# FPGA_1.net
KiCad netlist of a schematic drawn in Altium Designer
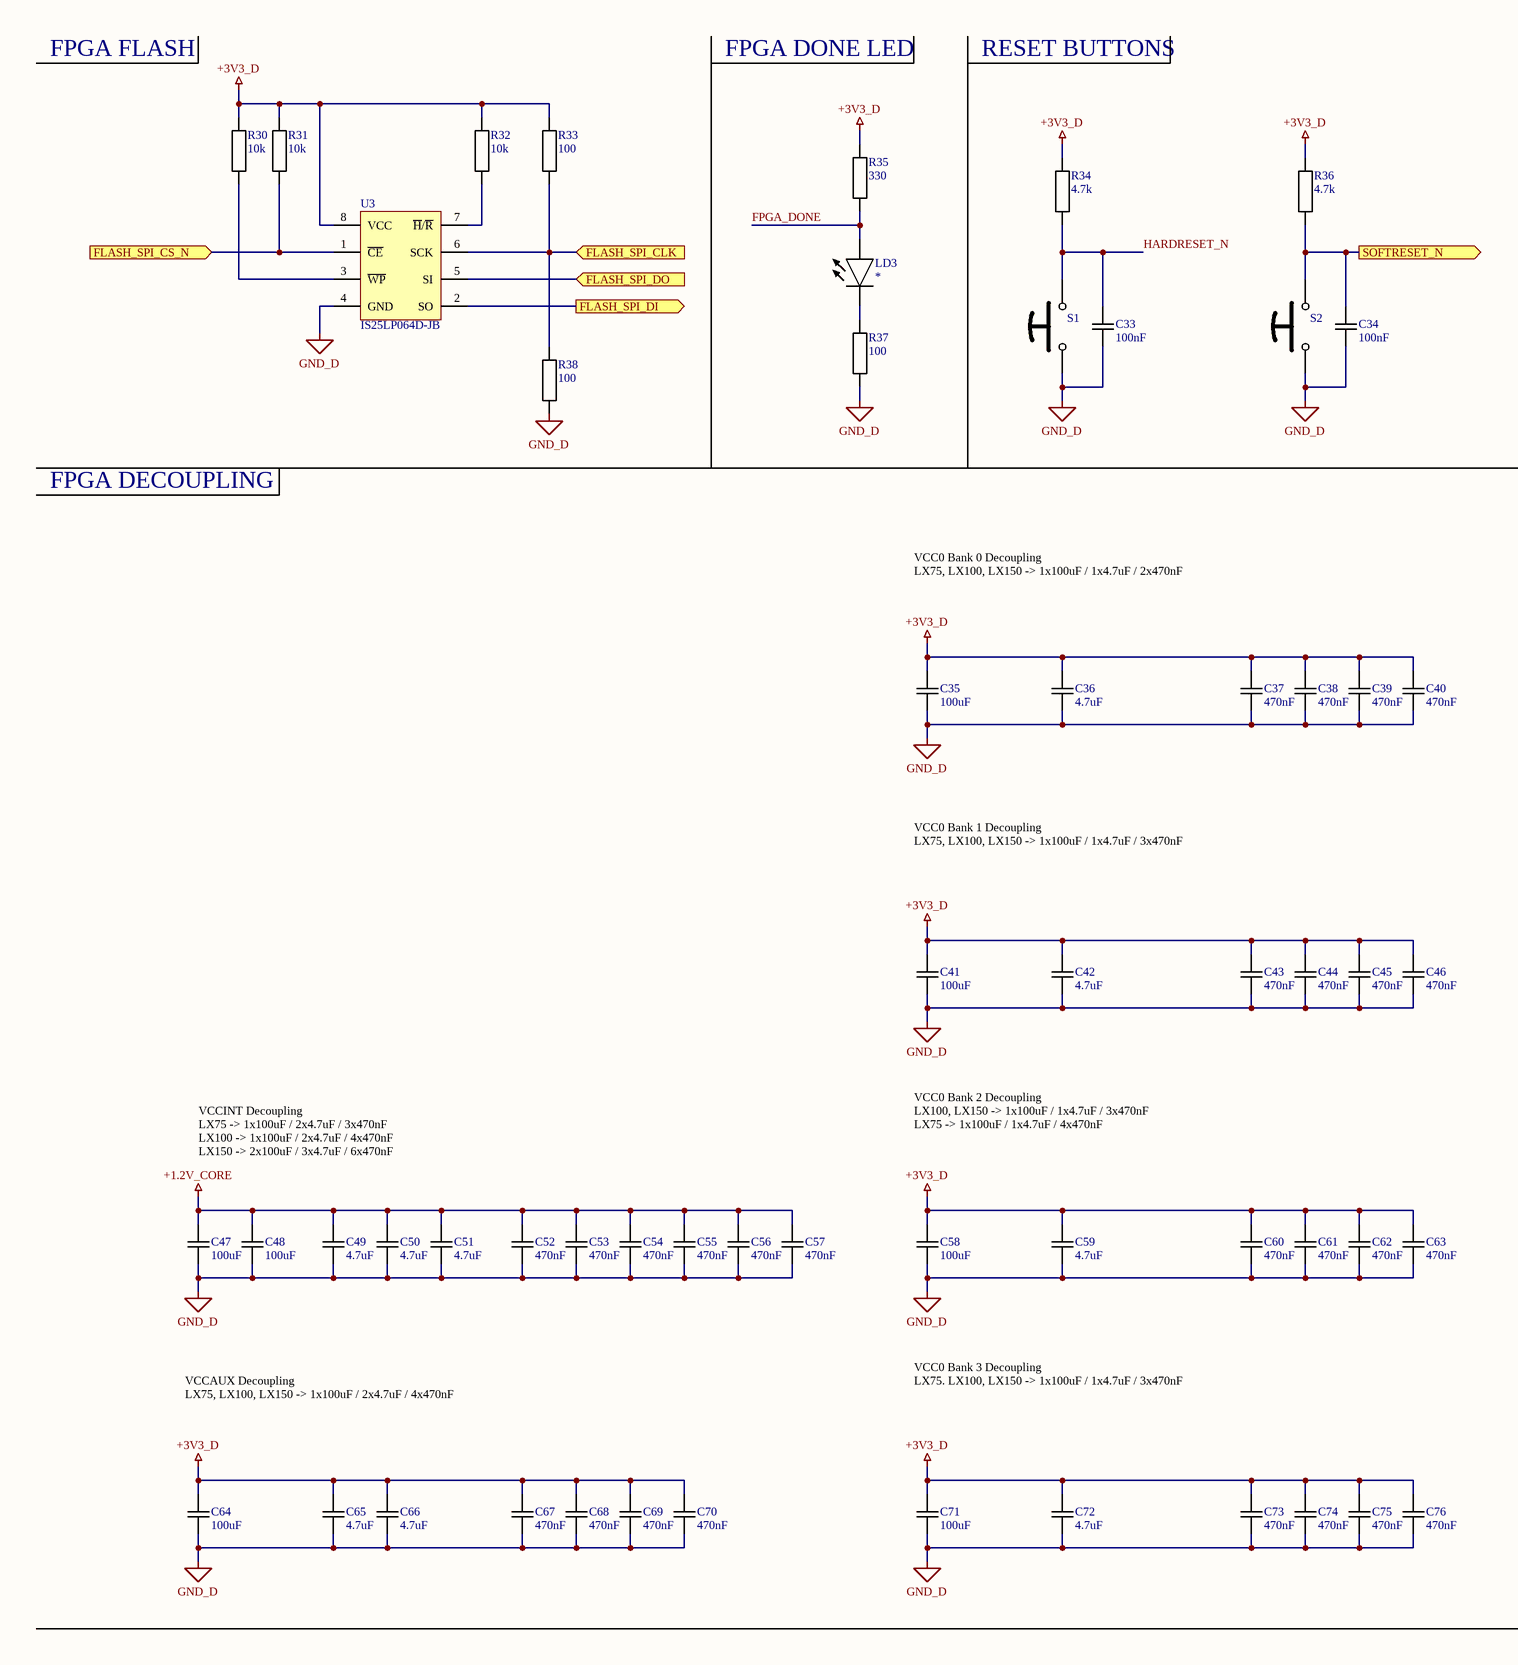
[diagram p0: FPGA_1.SchDoc, left]
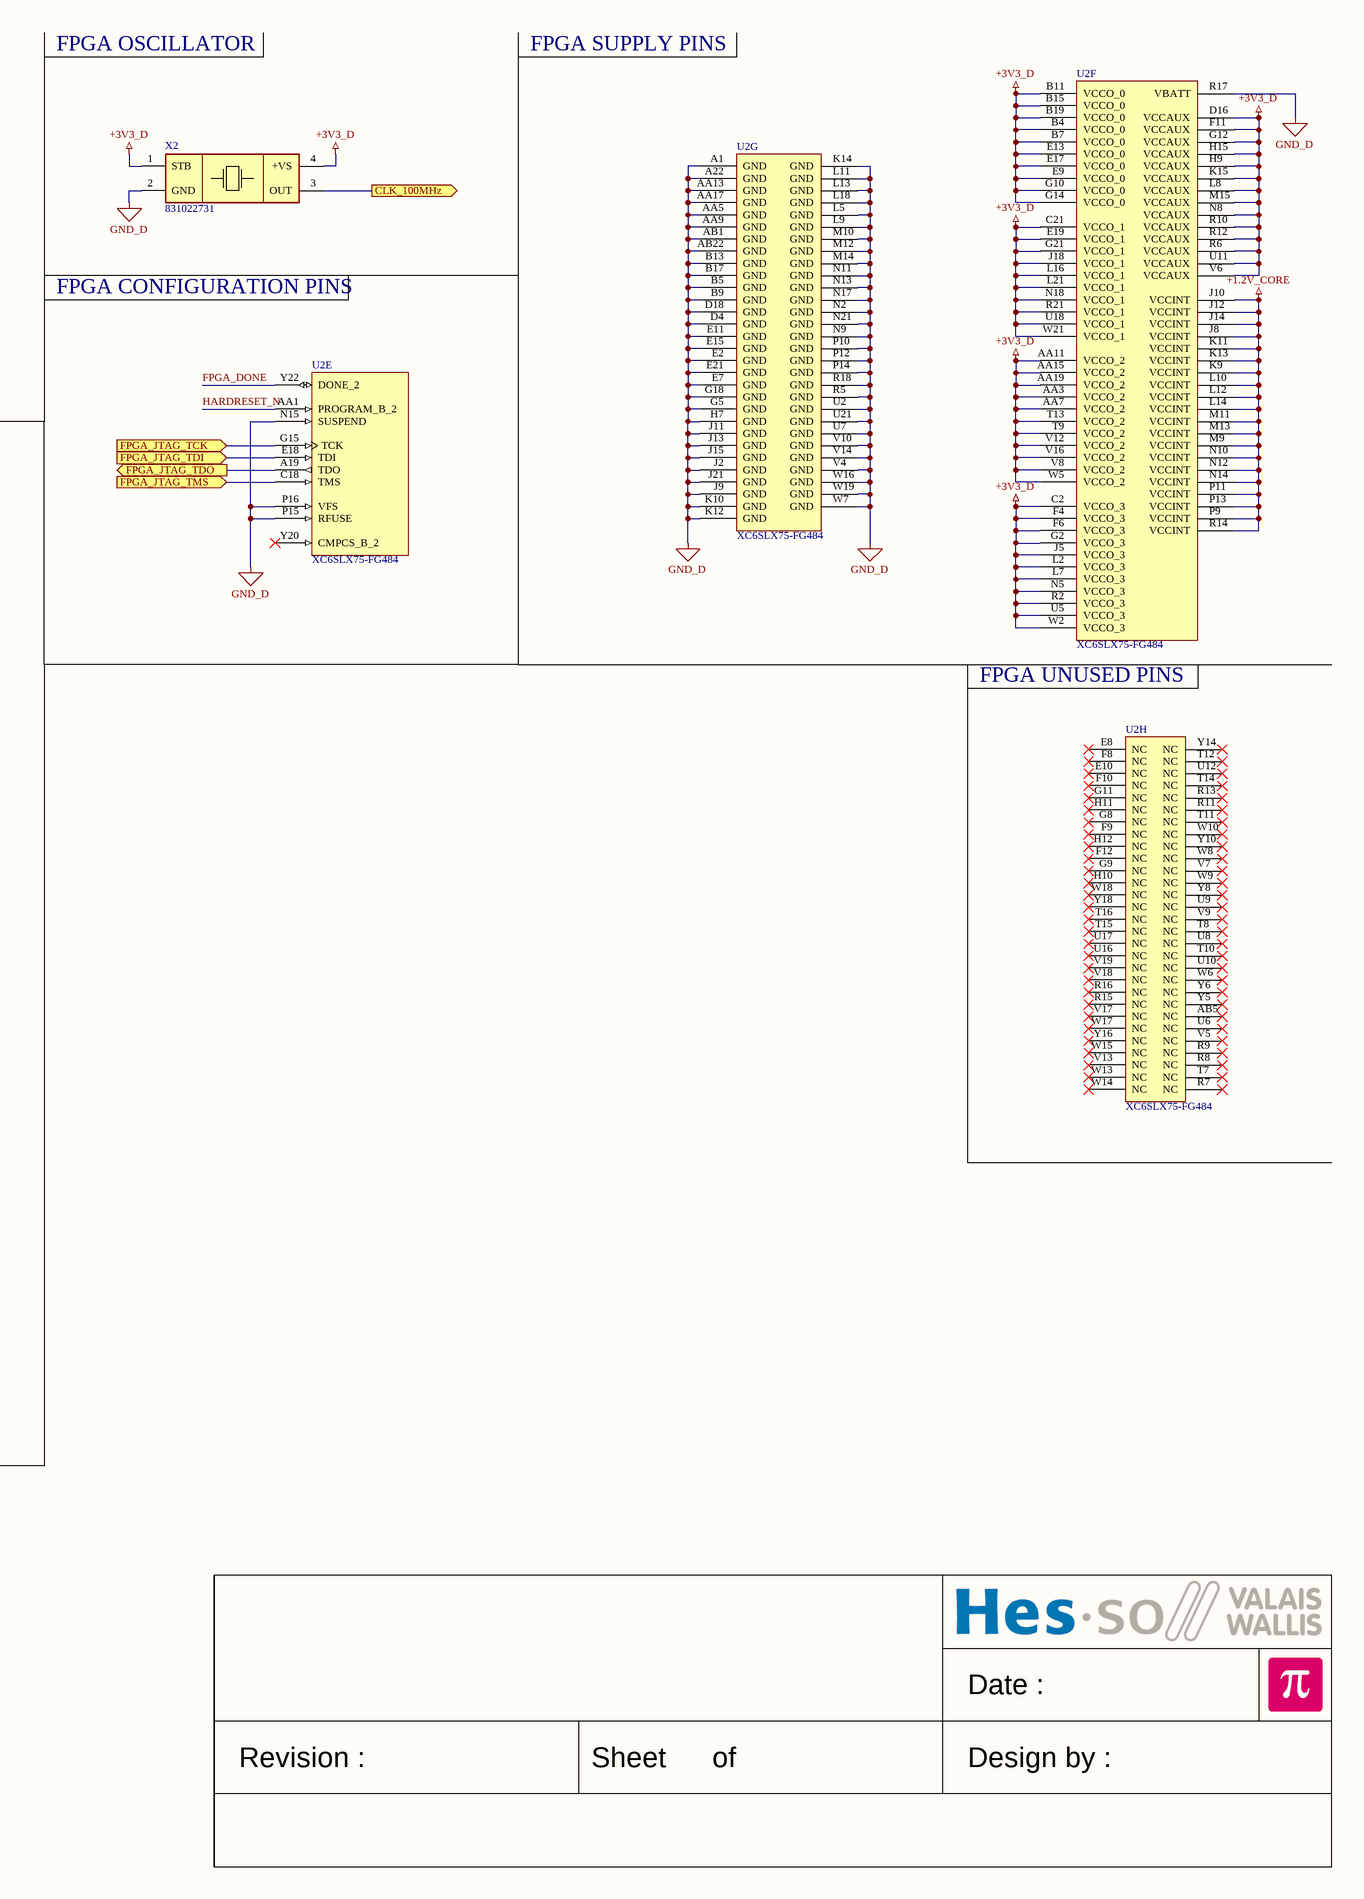
[diagram p1: FPGA_1.SchDoc, right]

(export (version "E")
  (design (tool "Eeschema 10.0.6"))
  (components
    (comp (ref "C33")
      (value "100nF")
      (footprint "CAPACITOR 1608 REFLOW")
      (description "Capacitor")
      (libsource (lib "Capacitor") (part "Capacitor"))
    )
    (comp (ref "C34")
      (value "100nF")
      (footprint "CAPACITOR 1608 REFLOW")
      (description "Capacitor")
      (libsource (lib "Capacitor") (part "Capacitor"))
    )
    (comp (ref "C35")
      (value "100uF")
      (footprint "CAPACITOR 3216 REFLOW")
      (description "Capacitor")
      (libsource (lib "Capacitor") (part "Capacitor"))
    )
    (comp (ref "C36")
      (value "4.7uF")
      (footprint "CAPACITOR 1608 REFLOW")
      (description "Capacitor")
      (libsource (lib "Capacitor") (part "Capacitor"))
    )
    (comp (ref "C37")
      (value "470nF")
      (footprint "CAPACITOR 1005 REFLOW")
      (description "Capacitor")
      (libsource (lib "Capacitor") (part "Capacitor"))
    )
    (comp (ref "C38")
      (value "470nF")
      (footprint "CAPACITOR 1005 REFLOW")
      (description "Capacitor")
      (libsource (lib "Capacitor") (part "Capacitor"))
    )
    (comp (ref "C39")
      (value "470nF")
      (footprint "CAPACITOR 1005 REFLOW")
      (description "Capacitor")
      (libsource (lib "Capacitor") (part "Capacitor"))
    )
    (comp (ref "C40")
      (value "470nF")
      (footprint "CAPACITOR 1005 REFLOW")
      (description "Capacitor")
      (libsource (lib "Capacitor") (part "Capacitor"))
    )
    (comp (ref "C41")
      (value "100uF")
      (footprint "CAPACITOR 3216 REFLOW")
      (description "Capacitor")
      (libsource (lib "Capacitor") (part "Capacitor"))
    )
    (comp (ref "C42")
      (value "4.7uF")
      (footprint "CAPACITOR 1608 REFLOW")
      (description "Capacitor")
      (libsource (lib "Capacitor") (part "Capacitor"))
    )
    (comp (ref "C43")
      (value "470nF")
      (footprint "CAPACITOR 1005 REFLOW")
      (description "Capacitor")
      (libsource (lib "Capacitor") (part "Capacitor"))
    )
    (comp (ref "C44")
      (value "470nF")
      (footprint "CAPACITOR 1005 REFLOW")
      (description "Capacitor")
      (libsource (lib "Capacitor") (part "Capacitor"))
    )
    (comp (ref "C45")
      (value "470nF")
      (footprint "CAPACITOR 1005 REFLOW")
      (description "Capacitor")
      (libsource (lib "Capacitor") (part "Capacitor"))
    )
    (comp (ref "C46")
      (value "470nF")
      (footprint "CAPACITOR 1005 REFLOW")
      (description "Capacitor")
      (libsource (lib "Capacitor") (part "Capacitor"))
    )
    (comp (ref "C47")
      (value "100uF")
      (footprint "CAPACITOR 3216 REFLOW")
      (description "Capacitor")
      (libsource (lib "Capacitor") (part "Capacitor"))
    )
    (comp (ref "C48")
      (value "100uF")
      (footprint "CAPACITOR 3216 REFLOW")
      (description "Capacitor")
      (libsource (lib "Capacitor") (part "Capacitor"))
    )
    (comp (ref "C49")
      (value "4.7uF")
      (footprint "CAPACITOR 1608 REFLOW")
      (description "Capacitor")
      (libsource (lib "Capacitor") (part "Capacitor"))
    )
    (comp (ref "C50")
      (value "4.7uF")
      (footprint "CAPACITOR 1608 REFLOW")
      (description "Capacitor")
      (libsource (lib "Capacitor") (part "Capacitor"))
    )
    (comp (ref "C51")
      (value "4.7uF")
      (footprint "CAPACITOR 1608 REFLOW")
      (description "Capacitor")
      (libsource (lib "Capacitor") (part "Capacitor"))
    )
    (comp (ref "C52")
      (value "470nF")
      (footprint "CAPACITOR 1005 REFLOW")
      (description "Capacitor")
      (libsource (lib "Capacitor") (part "Capacitor"))
    )
    (comp (ref "C53")
      (value "470nF")
      (footprint "CAPACITOR 1005 REFLOW")
      (description "Capacitor")
      (libsource (lib "Capacitor") (part "Capacitor"))
    )
    (comp (ref "C54")
      (value "470nF")
      (footprint "CAPACITOR 1005 REFLOW")
      (description "Capacitor")
      (libsource (lib "Capacitor") (part "Capacitor"))
    )
    (comp (ref "C55")
      (value "470nF")
      (footprint "CAPACITOR 1005 REFLOW")
      (description "Capacitor")
      (libsource (lib "Capacitor") (part "Capacitor"))
    )
    (comp (ref "C56")
      (value "470nF")
      (footprint "CAPACITOR 1005 REFLOW")
      (description "Capacitor")
      (libsource (lib "Capacitor") (part "Capacitor"))
    )
    (comp (ref "C57")
      (value "470nF")
      (footprint "CAPACITOR 1005 REFLOW")
      (description "Capacitor")
      (libsource (lib "Capacitor") (part "Capacitor"))
    )
    (comp (ref "C58")
      (value "100uF")
      (footprint "CAPACITOR 3216 REFLOW")
      (description "Capacitor")
      (libsource (lib "Capacitor") (part "Capacitor"))
    )
    (comp (ref "C59")
      (value "4.7uF")
      (footprint "CAPACITOR 1608 REFLOW")
      (description "Capacitor")
      (libsource (lib "Capacitor") (part "Capacitor"))
    )
    (comp (ref "C60")
      (value "470nF")
      (footprint "CAPACITOR 1005 REFLOW")
      (description "Capacitor")
      (libsource (lib "Capacitor") (part "Capacitor"))
    )
    (comp (ref "C61")
      (value "470nF")
      (footprint "CAPACITOR 1005 REFLOW")
      (description "Capacitor")
      (libsource (lib "Capacitor") (part "Capacitor"))
    )
    (comp (ref "C62")
      (value "470nF")
      (footprint "CAPACITOR 1005 REFLOW")
      (description "Capacitor")
      (libsource (lib "Capacitor") (part "Capacitor"))
    )
    (comp (ref "C63")
      (value "470nF")
      (footprint "CAPACITOR 1005 REFLOW")
      (description "Capacitor")
      (libsource (lib "Capacitor") (part "Capacitor"))
    )
    (comp (ref "C64")
      (value "100uF")
      (footprint "CAPACITOR 3216 REFLOW")
      (description "Capacitor")
      (libsource (lib "Capacitor") (part "Capacitor"))
    )
    (comp (ref "C65")
      (value "4.7uF")
      (footprint "CAPACITOR 1608 REFLOW")
      (description "Capacitor")
      (libsource (lib "Capacitor") (part "Capacitor"))
    )
    (comp (ref "C66")
      (value "4.7uF")
      (footprint "CAPACITOR 1608 REFLOW")
      (description "Capacitor")
      (libsource (lib "Capacitor") (part "Capacitor"))
    )
    (comp (ref "C67")
      (value "470nF")
      (footprint "CAPACITOR 1005 REFLOW")
      (description "Capacitor")
      (libsource (lib "Capacitor") (part "Capacitor"))
    )
    (comp (ref "C68")
      (value "470nF")
      (footprint "CAPACITOR 1005 REFLOW")
      (description "Capacitor")
      (libsource (lib "Capacitor") (part "Capacitor"))
    )
    (comp (ref "C69")
      (value "470nF")
      (footprint "CAPACITOR 1005 REFLOW")
      (description "Capacitor")
      (libsource (lib "Capacitor") (part "Capacitor"))
    )
    (comp (ref "C70")
      (value "470nF")
      (footprint "CAPACITOR 1005 REFLOW")
      (description "Capacitor")
      (libsource (lib "Capacitor") (part "Capacitor"))
    )
    (comp (ref "C71")
      (value "100uF")
      (footprint "CAPACITOR 3216 REFLOW")
      (description "Capacitor")
      (libsource (lib "Capacitor") (part "Capacitor"))
    )
    (comp (ref "C72")
      (value "4.7uF")
      (footprint "CAPACITOR 1608 REFLOW")
      (description "Capacitor")
      (libsource (lib "Capacitor") (part "Capacitor"))
    )
    (comp (ref "C73")
      (value "470nF")
      (footprint "CAPACITOR 1005 REFLOW")
      (description "Capacitor")
      (libsource (lib "Capacitor") (part "Capacitor"))
    )
    (comp (ref "C74")
      (value "470nF")
      (footprint "CAPACITOR 1005 REFLOW")
      (description "Capacitor")
      (libsource (lib "Capacitor") (part "Capacitor"))
    )
    (comp (ref "C75")
      (value "470nF")
      (footprint "CAPACITOR 1005 REFLOW")
      (description "Capacitor")
      (libsource (lib "Capacitor") (part "Capacitor"))
    )
    (comp (ref "C76")
      (value "470nF")
      (footprint "CAPACITOR 1005 REFLOW")
      (description "Capacitor")
      (libsource (lib "Capacitor") (part "Capacitor"))
    )
    (comp (ref "LD3")
      (value "*")
      (footprint "LED 1608 REFLOW")
      (description "LED generic")
      (libsource (lib "Diode") (part "LED"))
    )
    (comp (ref "R30")
      (value "10k")
      (footprint "RESISTOR 1608 REFLOW")
      (description "Resistor 1% 50V 100mW 1608(0603)")
      (libsource (lib "Resistor") (part "Resistor"))
    )
    (comp (ref "R31")
      (value "10k")
      (footprint "RESISTOR 1608 REFLOW")
      (description "Resistor 1% 50V 100mW 1608(0603)")
      (libsource (lib "Resistor") (part "Resistor"))
    )
    (comp (ref "R32")
      (value "10k")
      (footprint "RESISTOR 1608 REFLOW")
      (description "Resistor 1% 50V 100mW 1608(0603)")
      (libsource (lib "Resistor") (part "Resistor"))
    )
    (comp (ref "R33")
      (value "100")
      (footprint "RESISTOR 1608 REFLOW")
      (description "Resistor 1% 50V 100mW 1608(0603)")
      (libsource (lib "Resistor") (part "Resistor"))
    )
    (comp (ref "R34")
      (value "4.7k")
      (footprint "RESISTOR 2012 REFLOW")
      (description "Resistor 1% 50V 125mW 2012(0805)")
      (libsource (lib "Resistor") (part "Resistor"))
    )
    (comp (ref "R35")
      (value "330")
      (footprint "RESISTOR 2012 REFLOW")
      (description "Resistor 1% 50V 125mW 2012(0805)")
      (libsource (lib "Resistor") (part "Resistor"))
    )
    (comp (ref "R36")
      (value "4.7k")
      (footprint "RESISTOR 2012 REFLOW")
      (description "Resistor 1% 50V 125mW 2012(0805)")
      (libsource (lib "Resistor") (part "Resistor"))
    )
    (comp (ref "R37")
      (value "100")
      (footprint "RESISTOR 2012 REFLOW")
      (description "Resistor 1% 50V 125mW 2012(0805)")
      (libsource (lib "Resistor") (part "Resistor"))
    )
    (comp (ref "R38")
      (value "100")
      (footprint "RESISTOR 1608 REFLOW")
      (description "Resistor 1% 50V 100mW 1608(0603)")
      (libsource (lib "Resistor") (part "Resistor"))
    )
    (comp (ref "S1")
      (value "*")
      (footprint "Push Button C2.5X3.0 OMRON B3U-1000P(M)-B")
      (description "Push Button, 2 pins")
      (libsource (lib "Button") (part "Push Button 2Pins"))
    )
    (comp (ref "S2")
      (value "*")
      (footprint "Push Button C2.5X3.0 OMRON B3U-1000P(M)-B")
      (description "Push Button, 2 pins")
      (libsource (lib "Button") (part "Push Button 2Pins"))
    )
    (comp (ref "U2")
      (value "XC6SLX75-FG484")
      (footprint "BGA484 P1.0 C23X23 H2.2")
      (description "Spartan-6 LXT 1.2V FPGA, 268 User I/Os, 484-Ball Fine-Pitch BGA (1.0mm Pitch)")
      (libsource (lib "Processor") (part "XC6SLX75-FG484"))
    )
    (comp (ref "U3")
      (value "IS25LP064D-JB")
      (footprint "SO8 P1.27 C4.0X5.0 H1.75")
      (description "64Mb Serial Flash Memory")
      (libsource (lib "Memory") (part "IS25LP064D-JB"))
    )
    (comp (ref "X2")
      (value "831022731")
      (footprint "Oscillator C5.2x7.2 IQD LFSPXO")
      (description "Oscillator C5.2x7.2 IQD LFSPXO")
      (libsource (lib "Oscillator") (part "Oscillator C5.2x7.2 IQD LFSPXO"))
    )
  )
  (nets
    (net (code "1") (name "+1.2V_CORE") (class "Default")
      (node (ref "C47") (pin "1") (pinfunction "1_1") (pintype "passive"))
      (node (ref "C48") (pin "1") (pinfunction "1_1") (pintype "passive"))
      (node (ref "C49") (pin "1") (pinfunction "1_1") (pintype "passive"))
      (node (ref "C50") (pin "1") (pinfunction "1_1") (pintype "passive"))
      (node (ref "C51") (pin "1") (pinfunction "1_1") (pintype "passive"))
      (node (ref "C52") (pin "1") (pinfunction "1_1") (pintype "passive"))
      (node (ref "C53") (pin "1") (pinfunction "1_1") (pintype "passive"))
      (node (ref "C54") (pin "1") (pinfunction "1_1") (pintype "passive"))
      (node (ref "C55") (pin "1") (pinfunction "1_1") (pintype "passive"))
      (node (ref "C56") (pin "1") (pinfunction "1_1") (pintype "passive"))
      (node (ref "C57") (pin "1") (pinfunction "1_1") (pintype "passive"))
      (node (ref "U2") (pin "J10") (pinfunction "VCCINT_J10") (pintype "power_in"))
      (node (ref "U2") (pin "J12") (pinfunction "VCCINT_J12") (pintype "power_in"))
      (node (ref "U2") (pin "J14") (pinfunction "VCCINT_J14") (pintype "power_in"))
      (node (ref "U2") (pin "J8") (pinfunction "VCCINT_J8") (pintype "power_in"))
      (node (ref "U2") (pin "K11") (pinfunction "VCCINT_K11") (pintype "power_in"))
      (node (ref "U2") (pin "K13") (pinfunction "VCCINT_K13") (pintype "power_in"))
      (node (ref "U2") (pin "K9") (pinfunction "VCCINT_K9") (pintype "power_in"))
      (node (ref "U2") (pin "L10") (pinfunction "VCCINT_L10") (pintype "power_in"))
      (node (ref "U2") (pin "L12") (pinfunction "VCCINT_L12") (pintype "power_in"))
      (node (ref "U2") (pin "L14") (pinfunction "VCCINT_L14") (pintype "power_in"))
      (node (ref "U2") (pin "M11") (pinfunction "VCCINT_M11") (pintype "power_in"))
      (node (ref "U2") (pin "M13") (pinfunction "VCCINT_M13") (pintype "power_in"))
      (node (ref "U2") (pin "M9") (pinfunction "VCCINT_M9") (pintype "power_in"))
      (node (ref "U2") (pin "N10") (pinfunction "VCCINT_N10") (pintype "power_in"))
      (node (ref "U2") (pin "N12") (pinfunction "VCCINT_N12") (pintype "power_in"))
      (node (ref "U2") (pin "N14") (pinfunction "VCCINT_N14") (pintype "power_in"))
      (node (ref "U2") (pin "P11") (pinfunction "VCCINT_P11") (pintype "power_in"))
      (node (ref "U2") (pin "P13") (pinfunction "VCCINT_P13") (pintype "power_in"))
      (node (ref "U2") (pin "P9") (pinfunction "VCCINT_P9") (pintype "power_in"))
      (node (ref "U2") (pin "R14") (pinfunction "VCCINT_R14") (pintype "power_in"))
    )
    (net (code "2") (name "+3V3_D") (class "Default")
      (node (ref "C35") (pin "1") (pinfunction "1_1") (pintype "passive"))
      (node (ref "C36") (pin "1") (pinfunction "1_1") (pintype "passive"))
      (node (ref "C37") (pin "1") (pinfunction "1_1") (pintype "passive"))
      (node (ref "C38") (pin "1") (pinfunction "1_1") (pintype "passive"))
      (node (ref "C39") (pin "1") (pinfunction "1_1") (pintype "passive"))
      (node (ref "C40") (pin "1") (pinfunction "1_1") (pintype "passive"))
      (node (ref "C41") (pin "1") (pinfunction "1_1") (pintype "passive"))
      (node (ref "C42") (pin "1") (pinfunction "1_1") (pintype "passive"))
      (node (ref "C43") (pin "1") (pinfunction "1_1") (pintype "passive"))
      (node (ref "C44") (pin "1") (pinfunction "1_1") (pintype "passive"))
      (node (ref "C45") (pin "1") (pinfunction "1_1") (pintype "passive"))
      (node (ref "C46") (pin "1") (pinfunction "1_1") (pintype "passive"))
      (node (ref "C58") (pin "1") (pinfunction "1_1") (pintype "passive"))
      (node (ref "C59") (pin "1") (pinfunction "1_1") (pintype "passive"))
      (node (ref "C60") (pin "1") (pinfunction "1_1") (pintype "passive"))
      (node (ref "C61") (pin "1") (pinfunction "1_1") (pintype "passive"))
      (node (ref "C62") (pin "1") (pinfunction "1_1") (pintype "passive"))
      (node (ref "C63") (pin "1") (pinfunction "1_1") (pintype "passive"))
      (node (ref "C64") (pin "1") (pinfunction "1_1") (pintype "passive"))
      (node (ref "C65") (pin "1") (pinfunction "1_1") (pintype "passive"))
      (node (ref "C66") (pin "1") (pinfunction "1_1") (pintype "passive"))
      (node (ref "C67") (pin "1") (pinfunction "1_1") (pintype "passive"))
      (node (ref "C68") (pin "1") (pinfunction "1_1") (pintype "passive"))
      (node (ref "C69") (pin "1") (pinfunction "1_1") (pintype "passive"))
      (node (ref "C70") (pin "1") (pinfunction "1_1") (pintype "passive"))
      (node (ref "C71") (pin "1") (pinfunction "1_1") (pintype "passive"))
      (node (ref "C72") (pin "1") (pinfunction "1_1") (pintype "passive"))
      (node (ref "C73") (pin "1") (pinfunction "1_1") (pintype "passive"))
      (node (ref "C74") (pin "1") (pinfunction "1_1") (pintype "passive"))
      (node (ref "C75") (pin "1") (pinfunction "1_1") (pintype "passive"))
      (node (ref "C76") (pin "1") (pinfunction "1_1") (pintype "passive"))
      (node (ref "R30") (pin "2") (pinfunction "2_2") (pintype "passive"))
      (node (ref "R31") (pin "2") (pinfunction "2_2") (pintype "passive"))
      (node (ref "R32") (pin "2") (pinfunction "2_2") (pintype "passive"))
      (node (ref "R33") (pin "2") (pinfunction "2_2") (pintype "passive"))
      (node (ref "R34") (pin "2") (pinfunction "2_2") (pintype "passive"))
      (node (ref "R35") (pin "2") (pinfunction "2_2") (pintype "passive"))
      (node (ref "R36") (pin "2") (pinfunction "2_2") (pintype "passive"))
      (node (ref "U2") (pin "AA11") (pinfunction "VCCO_2_AA11") (pintype "power_in"))
      (node (ref "U2") (pin "AA15") (pinfunction "VCCO_2_AA15") (pintype "power_in"))
      (node (ref "U2") (pin "AA19") (pinfunction "VCCO_2_AA19") (pintype "power_in"))
      (node (ref "U2") (pin "AA3") (pinfunction "VCCO_2_AA3") (pintype "power_in"))
      (node (ref "U2") (pin "AA7") (pinfunction "VCCO_2_AA7") (pintype "power_in"))
      (node (ref "U2") (pin "B11") (pinfunction "VCCO_0_B11") (pintype "power_in"))
      (node (ref "U2") (pin "B15") (pinfunction "VCCO_0_B15") (pintype "power_in"))
      (node (ref "U2") (pin "B19") (pinfunction "VCCO_0_B19") (pintype "power_in"))
      (node (ref "U2") (pin "B4") (pinfunction "VCCO_0_B4") (pintype "power_in"))
      (node (ref "U2") (pin "B7") (pinfunction "VCCO_0_B7") (pintype "power_in"))
      (node (ref "U2") (pin "C2") (pinfunction "VCCO_3_C2") (pintype "power_in"))
      (node (ref "U2") (pin "C21") (pinfunction "VCCO_1_C21") (pintype "power_in"))
      (node (ref "U2") (pin "D16") (pinfunction "VCCAUX_D16") (pintype "power_in"))
      (node (ref "U2") (pin "E13") (pinfunction "VCCO_0_E13") (pintype "power_in"))
      (node (ref "U2") (pin "E17") (pinfunction "VCCO_0_E17") (pintype "power_in"))
      (node (ref "U2") (pin "E19") (pinfunction "VCCO_1_E19") (pintype "power_in"))
      (node (ref "U2") (pin "E9") (pinfunction "VCCO_0_E9") (pintype "power_in"))
      (node (ref "U2") (pin "F11") (pinfunction "VCCAUX_F11") (pintype "power_in"))
      (node (ref "U2") (pin "F4") (pinfunction "VCCO_3_F4") (pintype "power_in"))
      (node (ref "U2") (pin "F6") (pinfunction "VCCO_3_F6") (pintype "power_in"))
      (node (ref "U2") (pin "G10") (pinfunction "VCCO_0_G10") (pintype "power_in"))
      (node (ref "U2") (pin "G12") (pinfunction "VCCAUX_G12") (pintype "power_in"))
      (node (ref "U2") (pin "G14") (pinfunction "VCCO_0_G14") (pintype "power_in"))
      (node (ref "U2") (pin "G2") (pinfunction "VCCO_3_G2") (pintype "power_in"))
      (node (ref "U2") (pin "G21") (pinfunction "VCCO_1_G21") (pintype "power_in"))
      (node (ref "U2") (pin "H15") (pinfunction "VCCAUX_H15") (pintype "power_in"))
      (node (ref "U2") (pin "H9") (pinfunction "VCCAUX_H9") (pintype "power_in"))
      (node (ref "U2") (pin "J18") (pinfunction "VCCO_1_J18") (pintype "power_in"))
      (node (ref "U2") (pin "J5") (pinfunction "VCCO_3_J5") (pintype "power_in"))
      (node (ref "U2") (pin "K15") (pinfunction "VCCAUX_K15") (pintype "power_in"))
      (node (ref "U2") (pin "L16") (pinfunction "VCCO_1_L16") (pintype "power_in"))
      (node (ref "U2") (pin "L2") (pinfunction "VCCO_3_L2") (pintype "power_in"))
      (node (ref "U2") (pin "L21") (pinfunction "VCCO_1_L21") (pintype "power_in"))
      (node (ref "U2") (pin "L7") (pinfunction "VCCO_3_L7") (pintype "power_in"))
      (node (ref "U2") (pin "L8") (pinfunction "VCCAUX_L8") (pintype "power_in"))
      (node (ref "U2") (pin "M15") (pinfunction "VCCAUX_M15") (pintype "power_in"))
      (node (ref "U2") (pin "N18") (pinfunction "VCCO_1_N18") (pintype "power_in"))
      (node (ref "U2") (pin "N5") (pinfunction "VCCO_3_N5") (pintype "power_in"))
      (node (ref "U2") (pin "N8") (pinfunction "VCCAUX_N8") (pintype "power_in"))
      (node (ref "U2") (pin "R10") (pinfunction "VCCAUX_R10") (pintype "power_in"))
      (node (ref "U2") (pin "R12") (pinfunction "VCCAUX_R12") (pintype "power_in"))
      (node (ref "U2") (pin "R2") (pinfunction "VCCO_3_R2") (pintype "power_in"))
      (node (ref "U2") (pin "R21") (pinfunction "VCCO_1_R21") (pintype "power_in"))
      (node (ref "U2") (pin "R6") (pinfunction "VCCAUX_R6") (pintype "power_in"))
      (node (ref "U2") (pin "T13") (pinfunction "VCCO_2_T13") (pintype "power_in"))
      (node (ref "U2") (pin "T9") (pinfunction "VCCO_2_T9") (pintype "power_in"))
      (node (ref "U2") (pin "U11") (pinfunction "VCCAUX_U11") (pintype "power_in"))
      (node (ref "U2") (pin "U18") (pinfunction "VCCO_1_U18") (pintype "power_in"))
      (node (ref "U2") (pin "U5") (pinfunction "VCCO_3_U5") (pintype "power_in"))
      (node (ref "U2") (pin "V12") (pinfunction "VCCO_2_V12") (pintype "power_in"))
      (node (ref "U2") (pin "V16") (pinfunction "VCCO_2_V16") (pintype "power_in"))
      (node (ref "U2") (pin "V6") (pinfunction "VCCAUX_V6") (pintype "power_in"))
      (node (ref "U2") (pin "V8") (pinfunction "VCCO_2_V8") (pintype "power_in"))
      (node (ref "U2") (pin "W2") (pinfunction "VCCO_3_W2") (pintype "power_in"))
      (node (ref "U2") (pin "W21") (pinfunction "VCCO_1_W21") (pintype "power_in"))
      (node (ref "U2") (pin "W5") (pinfunction "VCCO_2_W5") (pintype "power_in"))
      (node (ref "U3") (pin "8") (pinfunction "VCC_8") (pintype "power_in"))
      (node (ref "X2") (pin "1") (pinfunction "STB_1") (pintype "passive"))
      (node (ref "X2") (pin "4") (pinfunction "+VS_4") (pintype "passive"))
    )
    (net (code "3") (name "/CLK_100MHz") (class "Default")
      (node (ref "X2") (pin "3") (pinfunction "OUT_3") (pintype "passive"))
    )
    (net (code "4") (name "/FLASH_SPI_CLK") (class "Default")
      (node (ref "R33") (pin "1") (pinfunction "1_1") (pintype "passive"))
      (node (ref "R38") (pin "2") (pinfunction "2_2") (pintype "passive"))
      (node (ref "U3") (pin "6") (pinfunction "SCK_6") (pintype "passive"))
    )
    (net (code "5") (name "/FLASH_SPI_CS_N") (class "Default")
      (node (ref "R31") (pin "1") (pinfunction "1_1") (pintype "passive"))
      (node (ref "U3") (pin "1") (pinfunction "~{CE}_1") (pintype "passive"))
    )
    (net (code "6") (name "/FLASH_SPI_DI") (class "Default")
      (node (ref "U3") (pin "2") (pinfunction "SO_2") (pintype "passive"))
    )
    (net (code "7") (name "/FLASH_SPI_DO") (class "Default")
      (node (ref "U3") (pin "5") (pinfunction "SI_5") (pintype "passive"))
    )
    (net (code "8") (name "/FPGA_DONE") (class "Default")
      (node (ref "LD3") (pin "2") (pinfunction "A_2") (pintype "passive"))
      (node (ref "R35") (pin "1") (pinfunction "1_1") (pintype "passive"))
      (node (ref "U2") (pin "Y22") (pinfunction "DONE_2_Y22") (pintype "bidirectional"))
    )
    (net (code "9") (name "/FPGA_JTAG_TCK") (class "Default")
      (node (ref "U2") (pin "G15") (pinfunction "TCK_G15") (pintype "input"))
    )
    (net (code "10") (name "/FPGA_JTAG_TDI") (class "Default")
      (node (ref "U2") (pin "E18") (pinfunction "TDI_E18") (pintype "input"))
    )
    (net (code "11") (name "/FPGA_JTAG_TDO") (class "Default")
      (node (ref "U2") (pin "A19") (pinfunction "TDO_A19") (pintype "output"))
    )
    (net (code "12") (name "/FPGA_JTAG_TMS") (class "Default")
      (node (ref "U2") (pin "C18") (pinfunction "TMS_C18") (pintype "input"))
    )
    (net (code "13") (name "/HARDRESET_N") (class "Default")
      (node (ref "C33") (pin "2") (pinfunction "2_2") (pintype "passive"))
      (node (ref "R34") (pin "1") (pinfunction "1_1") (pintype "passive"))
      (node (ref "S1") (pin "2") (pinfunction "2_2") (pintype "passive"))
      (node (ref "U2") (pin "AA1") (pinfunction "PROGRAM_B_2_AA1") (pintype "input"))
    )
    (net (code "14") (name "/SOFTRESET_N") (class "Default")
      (node (ref "C34") (pin "2") (pinfunction "2_2") (pintype "passive"))
      (node (ref "R36") (pin "1") (pinfunction "1_1") (pintype "passive"))
      (node (ref "S2") (pin "2") (pinfunction "2_2") (pintype "passive"))
    )
    (net (code "15") (name "GND_D") (class "Default")
      (node (ref "C33") (pin "1") (pinfunction "1_1") (pintype "passive"))
      (node (ref "C34") (pin "1") (pinfunction "1_1") (pintype "passive"))
      (node (ref "C35") (pin "2") (pinfunction "2_2") (pintype "passive"))
      (node (ref "C36") (pin "2") (pinfunction "2_2") (pintype "passive"))
      (node (ref "C37") (pin "2") (pinfunction "2_2") (pintype "passive"))
      (node (ref "C38") (pin "2") (pinfunction "2_2") (pintype "passive"))
      (node (ref "C39") (pin "2") (pinfunction "2_2") (pintype "passive"))
      (node (ref "C40") (pin "2") (pinfunction "2_2") (pintype "passive"))
      (node (ref "C41") (pin "2") (pinfunction "2_2") (pintype "passive"))
      (node (ref "C42") (pin "2") (pinfunction "2_2") (pintype "passive"))
      (node (ref "C43") (pin "2") (pinfunction "2_2") (pintype "passive"))
      (node (ref "C44") (pin "2") (pinfunction "2_2") (pintype "passive"))
      (node (ref "C45") (pin "2") (pinfunction "2_2") (pintype "passive"))
      (node (ref "C46") (pin "2") (pinfunction "2_2") (pintype "passive"))
      (node (ref "C47") (pin "2") (pinfunction "2_2") (pintype "passive"))
      (node (ref "C48") (pin "2") (pinfunction "2_2") (pintype "passive"))
      (node (ref "C49") (pin "2") (pinfunction "2_2") (pintype "passive"))
      (node (ref "C50") (pin "2") (pinfunction "2_2") (pintype "passive"))
      (node (ref "C51") (pin "2") (pinfunction "2_2") (pintype "passive"))
      (node (ref "C52") (pin "2") (pinfunction "2_2") (pintype "passive"))
      (node (ref "C53") (pin "2") (pinfunction "2_2") (pintype "passive"))
      (node (ref "C54") (pin "2") (pinfunction "2_2") (pintype "passive"))
      (node (ref "C55") (pin "2") (pinfunction "2_2") (pintype "passive"))
      (node (ref "C56") (pin "2") (pinfunction "2_2") (pintype "passive"))
      (node (ref "C57") (pin "2") (pinfunction "2_2") (pintype "passive"))
      (node (ref "C58") (pin "2") (pinfunction "2_2") (pintype "passive"))
      (node (ref "C59") (pin "2") (pinfunction "2_2") (pintype "passive"))
      (node (ref "C60") (pin "2") (pinfunction "2_2") (pintype "passive"))
      (node (ref "C61") (pin "2") (pinfunction "2_2") (pintype "passive"))
      (node (ref "C62") (pin "2") (pinfunction "2_2") (pintype "passive"))
      (node (ref "C63") (pin "2") (pinfunction "2_2") (pintype "passive"))
      (node (ref "C64") (pin "2") (pinfunction "2_2") (pintype "passive"))
      (node (ref "C65") (pin "2") (pinfunction "2_2") (pintype "passive"))
      (node (ref "C66") (pin "2") (pinfunction "2_2") (pintype "passive"))
      (node (ref "C67") (pin "2") (pinfunction "2_2") (pintype "passive"))
      (node (ref "C68") (pin "2") (pinfunction "2_2") (pintype "passive"))
      (node (ref "C69") (pin "2") (pinfunction "2_2") (pintype "passive"))
      (node (ref "C70") (pin "2") (pinfunction "2_2") (pintype "passive"))
      (node (ref "C71") (pin "2") (pinfunction "2_2") (pintype "passive"))
      (node (ref "C72") (pin "2") (pinfunction "2_2") (pintype "passive"))
      (node (ref "C73") (pin "2") (pinfunction "2_2") (pintype "passive"))
      (node (ref "C74") (pin "2") (pinfunction "2_2") (pintype "passive"))
      (node (ref "C75") (pin "2") (pinfunction "2_2") (pintype "passive"))
      (node (ref "C76") (pin "2") (pinfunction "2_2") (pintype "passive"))
      (node (ref "R37") (pin "1") (pinfunction "1_1") (pintype "passive"))
      (node (ref "R38") (pin "1") (pinfunction "1_1") (pintype "passive"))
      (node (ref "S1") (pin "1") (pinfunction "1_1") (pintype "passive"))
      (node (ref "S2") (pin "1") (pinfunction "1_1") (pintype "passive"))
      (node (ref "U2") (pin "A1") (pinfunction "GND_A1") (pintype "power_in"))
      (node (ref "U2") (pin "A22") (pinfunction "GND_A22") (pintype "power_in"))
      (node (ref "U2") (pin "AA13") (pinfunction "GND_AA13") (pintype "power_in"))
      (node (ref "U2") (pin "AA17") (pinfunction "GND_AA17") (pintype "power_in"))
      (node (ref "U2") (pin "AA5") (pinfunction "GND_AA5") (pintype "power_in"))
      (node (ref "U2") (pin "AA9") (pinfunction "GND_AA9") (pintype "power_in"))
      (node (ref "U2") (pin "AB1") (pinfunction "GND_AB1") (pintype "power_in"))
      (node (ref "U2") (pin "AB22") (pinfunction "GND_AB22") (pintype "power_in"))
      (node (ref "U2") (pin "B13") (pinfunction "GND_B13") (pintype "power_in"))
      (node (ref "U2") (pin "B17") (pinfunction "GND_B17") (pintype "power_in"))
      (node (ref "U2") (pin "B5") (pinfunction "GND_B5") (pintype "power_in"))
      (node (ref "U2") (pin "B9") (pinfunction "GND_B9") (pintype "power_in"))
      (node (ref "U2") (pin "D18") (pinfunction "GND_D18") (pintype "power_in"))
      (node (ref "U2") (pin "D4") (pinfunction "GND_D4") (pintype "power_in"))
      (node (ref "U2") (pin "E11") (pinfunction "GND_E11") (pintype "power_in"))
      (node (ref "U2") (pin "E15") (pinfunction "GND_E15") (pintype "power_in"))
      (node (ref "U2") (pin "E2") (pinfunction "GND_E2") (pintype "power_in"))
      (node (ref "U2") (pin "E21") (pinfunction "GND_E21") (pintype "power_in"))
      (node (ref "U2") (pin "E7") (pinfunction "GND_E7") (pintype "power_in"))
      (node (ref "U2") (pin "G18") (pinfunction "GND_G18") (pintype "power_in"))
      (node (ref "U2") (pin "G5") (pinfunction "GND_G5") (pintype "power_in"))
      (node (ref "U2") (pin "H7") (pinfunction "GND_H7") (pintype "power_in"))
      (node (ref "U2") (pin "J11") (pinfunction "GND_J11") (pintype "power_in"))
      (node (ref "U2") (pin "J13") (pinfunction "GND_J13") (pintype "power_in"))
      (node (ref "U2") (pin "J15") (pinfunction "GND_J15") (pintype "power_in"))
      (node (ref "U2") (pin "J2") (pinfunction "GND_J2") (pintype "power_in"))
      (node (ref "U2") (pin "J21") (pinfunction "GND_J21") (pintype "power_in"))
      (node (ref "U2") (pin "J9") (pinfunction "GND_J9") (pintype "power_in"))
      (node (ref "U2") (pin "K10") (pinfunction "GND_K10") (pintype "power_in"))
      (node (ref "U2") (pin "K12") (pinfunction "GND_K12") (pintype "power_in"))
      (node (ref "U2") (pin "K14") (pinfunction "GND_K14") (pintype "power_in"))
      (node (ref "U2") (pin "L11") (pinfunction "GND_L11") (pintype "power_in"))
      (node (ref "U2") (pin "L13") (pinfunction "GND_L13") (pintype "power_in"))
      (node (ref "U2") (pin "L18") (pinfunction "GND_L18") (pintype "power_in"))
      (node (ref "U2") (pin "L5") (pinfunction "GND_L5") (pintype "power_in"))
      (node (ref "U2") (pin "L9") (pinfunction "GND_L9") (pintype "power_in"))
      (node (ref "U2") (pin "M10") (pinfunction "GND_M10") (pintype "power_in"))
      (node (ref "U2") (pin "M12") (pinfunction "GND_M12") (pintype "power_in"))
      (node (ref "U2") (pin "M14") (pinfunction "GND_M14") (pintype "power_in"))
      (node (ref "U2") (pin "N11") (pinfunction "GND_N11") (pintype "power_in"))
      (node (ref "U2") (pin "N13") (pinfunction "GND_N13") (pintype "power_in"))
      (node (ref "U2") (pin "N15") (pinfunction "SUSPEND_N15") (pintype "input"))
      (node (ref "U2") (pin "N17") (pinfunction "GND_N17") (pintype "power_in"))
      (node (ref "U2") (pin "N2") (pinfunction "GND_N2") (pintype "power_in"))
      (node (ref "U2") (pin "N21") (pinfunction "GND_N21") (pintype "power_in"))
      (node (ref "U2") (pin "N9") (pinfunction "GND_N9") (pintype "power_in"))
      (node (ref "U2") (pin "P10") (pinfunction "GND_P10") (pintype "power_in"))
      (node (ref "U2") (pin "P12") (pinfunction "GND_P12") (pintype "power_in"))
      (node (ref "U2") (pin "P14") (pinfunction "GND_P14") (pintype "power_in"))
      (node (ref "U2") (pin "P15") (pinfunction "RFUSE_P15") (pintype "input"))
      (node (ref "U2") (pin "P16") (pinfunction "VFS_P16") (pintype "input"))
      (node (ref "U2") (pin "R17") (pinfunction "VBATT_R17") (pintype "power_in"))
      (node (ref "U2") (pin "R18") (pinfunction "GND_R18") (pintype "power_in"))
      (node (ref "U2") (pin "R5") (pinfunction "GND_R5") (pintype "power_in"))
      (node (ref "U2") (pin "U2") (pinfunction "GND_U2") (pintype "power_in"))
      (node (ref "U2") (pin "U21") (pinfunction "GND_U21") (pintype "power_in"))
      (node (ref "U2") (pin "U7") (pinfunction "GND_U7") (pintype "power_in"))
      (node (ref "U2") (pin "V10") (pinfunction "GND_V10") (pintype "power_in"))
      (node (ref "U2") (pin "V14") (pinfunction "GND_V14") (pintype "power_in"))
      (node (ref "U2") (pin "V4") (pinfunction "GND_V4") (pintype "power_in"))
      (node (ref "U2") (pin "W16") (pinfunction "GND_W16") (pintype "power_in"))
      (node (ref "U2") (pin "W19") (pinfunction "GND_W19") (pintype "power_in"))
      (node (ref "U2") (pin "W7") (pinfunction "GND_W7") (pintype "power_in"))
      (node (ref "U3") (pin "4") (pinfunction "GND_4") (pintype "power_in"))
      (node (ref "X2") (pin "2") (pinfunction "GND_2") (pintype "passive"))
    )
    (net (code "16") (name "Net-(LD3-C)") (class "Default")
      (node (ref "LD3") (pin "1") (pinfunction "C_1") (pintype "passive"))
      (node (ref "R37") (pin "2") (pinfunction "2_2") (pintype "passive"))
    )
    (net (code "17") (name "Net-(U3-~{H}{slash}~{R})") (class "Default")
      (node (ref "R32") (pin "1") (pinfunction "1_1") (pintype "passive"))
      (node (ref "U3") (pin "7") (pinfunction "~{H}/~{R}_7") (pintype "passive"))
    )
    (net (code "18") (name "Net-(U3-~{WP})") (class "Default")
      (node (ref "R30") (pin "1") (pinfunction "1_1") (pintype "passive"))
      (node (ref "U3") (pin "3") (pinfunction "~{WP}_3") (pintype "passive"))
    )
    (net (code "19") (name "unconnected-(U2E-CMPCS_B_2-PadY20)") (class "Default")
      (node (ref "U2") (pin "Y20") (pinfunction "CMPCS_B_2_Y20") (pintype "input+no_connect"))
    )
    (net (code "20") (name "unconnected-(U2H-NC-PadAB5)") (class "Default")
      (node (ref "U2") (pin "AB5") (pinfunction "NC_AB5") (pintype "passive+no_connect"))
    )
    (net (code "21") (name "unconnected-(U2H-NC-PadE8)") (class "Default")
      (node (ref "U2") (pin "E8") (pinfunction "NC_E8") (pintype "passive+no_connect"))
    )
    (net (code "22") (name "unconnected-(U2H-NC-PadE10)") (class "Default")
      (node (ref "U2") (pin "E10") (pinfunction "NC_E10") (pintype "passive+no_connect"))
    )
    (net (code "23") (name "unconnected-(U2H-NC-PadF8)") (class "Default")
      (node (ref "U2") (pin "F8") (pinfunction "NC_F8") (pintype "passive+no_connect"))
    )
    (net (code "24") (name "unconnected-(U2H-NC-PadF9)") (class "Default")
      (node (ref "U2") (pin "F9") (pinfunction "NC_F9") (pintype "passive+no_connect"))
    )
    (net (code "25") (name "unconnected-(U2H-NC-PadF10)") (class "Default")
      (node (ref "U2") (pin "F10") (pinfunction "NC_F10") (pintype "passive+no_connect"))
    )
    (net (code "26") (name "unconnected-(U2H-NC-PadF12)") (class "Default")
      (node (ref "U2") (pin "F12") (pinfunction "NC_F12") (pintype "passive+no_connect"))
    )
    (net (code "27") (name "unconnected-(U2H-NC-PadG8)") (class "Default")
      (node (ref "U2") (pin "G8") (pinfunction "NC_G8") (pintype "passive+no_connect"))
    )
    (net (code "28") (name "unconnected-(U2H-NC-PadG9)") (class "Default")
      (node (ref "U2") (pin "G9") (pinfunction "NC_G9") (pintype "passive+no_connect"))
    )
    (net (code "29") (name "unconnected-(U2H-NC-PadG11)") (class "Default")
      (node (ref "U2") (pin "G11") (pinfunction "NC_G11") (pintype "passive+no_connect"))
    )
    (net (code "30") (name "unconnected-(U2H-NC-PadH10)") (class "Default")
      (node (ref "U2") (pin "H10") (pinfunction "NC_H10") (pintype "passive+no_connect"))
    )
    (net (code "31") (name "unconnected-(U2H-NC-PadH11)") (class "Default")
      (node (ref "U2") (pin "H11") (pinfunction "NC_H11") (pintype "passive+no_connect"))
    )
    (net (code "32") (name "unconnected-(U2H-NC-PadH12)") (class "Default")
      (node (ref "U2") (pin "H12") (pinfunction "NC_H12") (pintype "passive+no_connect"))
    )
    (net (code "33") (name "unconnected-(U2H-NC-PadR7)") (class "Default")
      (node (ref "U2") (pin "R7") (pinfunction "NC_R7") (pintype "passive+no_connect"))
    )
    (net (code "34") (name "unconnected-(U2H-NC-PadR8)") (class "Default")
      (node (ref "U2") (pin "R8") (pinfunction "NC_R8") (pintype "passive+no_connect"))
    )
    (net (code "35") (name "unconnected-(U2H-NC-PadR9)") (class "Default")
      (node (ref "U2") (pin "R9") (pinfunction "NC_R9") (pintype "passive+no_connect"))
    )
    (net (code "36") (name "unconnected-(U2H-NC-PadR11)") (class "Default")
      (node (ref "U2") (pin "R11") (pinfunction "NC_R11") (pintype "passive+no_connect"))
    )
    (net (code "37") (name "unconnected-(U2H-NC-PadR13)") (class "Default")
      (node (ref "U2") (pin "R13") (pinfunction "NC_R13") (pintype "passive+no_connect"))
    )
    (net (code "38") (name "unconnected-(U2H-NC-PadR15)") (class "Default")
      (node (ref "U2") (pin "R15") (pinfunction "NC_R15") (pintype "passive+no_connect"))
    )
    (net (code "39") (name "unconnected-(U2H-NC-PadR16)") (class "Default")
      (node (ref "U2") (pin "R16") (pinfunction "NC_R16") (pintype "passive+no_connect"))
    )
    (net (code "40") (name "unconnected-(U2H-NC-PadT7)") (class "Default")
      (node (ref "U2") (pin "T7") (pinfunction "NC_T7") (pintype "passive+no_connect"))
    )
    (net (code "41") (name "unconnected-(U2H-NC-PadT8)") (class "Default")
      (node (ref "U2") (pin "T8") (pinfunction "NC_T8") (pintype "passive+no_connect"))
    )
    (net (code "42") (name "unconnected-(U2H-NC-PadT10)") (class "Default")
      (node (ref "U2") (pin "T10") (pinfunction "NC_T10") (pintype "passive+no_connect"))
    )
    (net (code "43") (name "unconnected-(U2H-NC-PadT11)") (class "Default")
      (node (ref "U2") (pin "T11") (pinfunction "NC_T11") (pintype "passive+no_connect"))
    )
    (net (code "44") (name "unconnected-(U2H-NC-PadT12)") (class "Default")
      (node (ref "U2") (pin "T12") (pinfunction "NC_T12") (pintype "passive+no_connect"))
    )
    (net (code "45") (name "unconnected-(U2H-NC-PadT14)") (class "Default")
      (node (ref "U2") (pin "T14") (pinfunction "NC_T14") (pintype "passive+no_connect"))
    )
    (net (code "46") (name "unconnected-(U2H-NC-PadT15)") (class "Default")
      (node (ref "U2") (pin "T15") (pinfunction "NC_T15") (pintype "passive+no_connect"))
    )
    (net (code "47") (name "unconnected-(U2H-NC-PadT16)") (class "Default")
      (node (ref "U2") (pin "T16") (pinfunction "NC_T16") (pintype "passive+no_connect"))
    )
    (net (code "48") (name "unconnected-(U2H-NC-PadU6)") (class "Default")
      (node (ref "U2") (pin "U6") (pinfunction "NC_U6") (pintype "passive+no_connect"))
    )
    (net (code "49") (name "unconnected-(U2H-NC-PadU8)") (class "Default")
      (node (ref "U2") (pin "U8") (pinfunction "NC_U8") (pintype "passive+no_connect"))
    )
    (net (code "50") (name "unconnected-(U2H-NC-PadU9)") (class "Default")
      (node (ref "U2") (pin "U9") (pinfunction "NC_U9") (pintype "passive+no_connect"))
    )
    (net (code "51") (name "unconnected-(U2H-NC-PadU10)") (class "Default")
      (node (ref "U2") (pin "U10") (pinfunction "NC_U10") (pintype "passive+no_connect"))
    )
    (net (code "52") (name "unconnected-(U2H-NC-PadU12)") (class "Default")
      (node (ref "U2") (pin "U12") (pinfunction "NC_U12") (pintype "passive+no_connect"))
    )
    (net (code "53") (name "unconnected-(U2H-NC-PadU16)") (class "Default")
      (node (ref "U2") (pin "U16") (pinfunction "NC_U16") (pintype "passive+no_connect"))
    )
    (net (code "54") (name "unconnected-(U2H-NC-PadU17)") (class "Default")
      (node (ref "U2") (pin "U17") (pinfunction "NC_U17") (pintype "passive+no_connect"))
    )
    (net (code "55") (name "unconnected-(U2H-NC-PadV5)") (class "Default")
      (node (ref "U2") (pin "V5") (pinfunction "NC_V5") (pintype "passive+no_connect"))
    )
    (net (code "56") (name "unconnected-(U2H-NC-PadV7)") (class "Default")
      (node (ref "U2") (pin "V7") (pinfunction "NC_V7") (pintype "passive+no_connect"))
    )
    (net (code "57") (name "unconnected-(U2H-NC-PadV9)") (class "Default")
      (node (ref "U2") (pin "V9") (pinfunction "NC_V9") (pintype "passive+no_connect"))
    )
    (net (code "58") (name "unconnected-(U2H-NC-PadV13)") (class "Default")
      (node (ref "U2") (pin "V13") (pinfunction "NC_V13") (pintype "passive+no_connect"))
    )
    (net (code "59") (name "unconnected-(U2H-NC-PadV17)") (class "Default")
      (node (ref "U2") (pin "V17") (pinfunction "NC_V17") (pintype "passive+no_connect"))
    )
    (net (code "60") (name "unconnected-(U2H-NC-PadV18)") (class "Default")
      (node (ref "U2") (pin "V18") (pinfunction "NC_V18") (pintype "passive+no_connect"))
    )
    (net (code "61") (name "unconnected-(U2H-NC-PadV19)") (class "Default")
      (node (ref "U2") (pin "V19") (pinfunction "NC_V19") (pintype "passive+no_connect"))
    )
    (net (code "62") (name "unconnected-(U2H-NC-PadW6)") (class "Default")
      (node (ref "U2") (pin "W6") (pinfunction "NC_W6") (pintype "passive+no_connect"))
    )
    (net (code "63") (name "unconnected-(U2H-NC-PadW8)") (class "Default")
      (node (ref "U2") (pin "W8") (pinfunction "NC_W8") (pintype "passive+no_connect"))
    )
    (net (code "64") (name "unconnected-(U2H-NC-PadW9)") (class "Default")
      (node (ref "U2") (pin "W9") (pinfunction "NC_W9") (pintype "passive+no_connect"))
    )
    (net (code "65") (name "unconnected-(U2H-NC-PadW10)") (class "Default")
      (node (ref "U2") (pin "W10") (pinfunction "NC_W10") (pintype "passive+no_connect"))
    )
    (net (code "66") (name "unconnected-(U2H-NC-PadW13)") (class "Default")
      (node (ref "U2") (pin "W13") (pinfunction "NC_W13") (pintype "passive+no_connect"))
    )
    (net (code "67") (name "unconnected-(U2H-NC-PadW14)") (class "Default")
      (node (ref "U2") (pin "W14") (pinfunction "NC_W14") (pintype "passive+no_connect"))
    )
    (net (code "68") (name "unconnected-(U2H-NC-PadW15)") (class "Default")
      (node (ref "U2") (pin "W15") (pinfunction "NC_W15") (pintype "passive+no_connect"))
    )
    (net (code "69") (name "unconnected-(U2H-NC-PadW17)") (class "Default")
      (node (ref "U2") (pin "W17") (pinfunction "NC_W17") (pintype "passive+no_connect"))
    )
    (net (code "70") (name "unconnected-(U2H-NC-PadW18)") (class "Default")
      (node (ref "U2") (pin "W18") (pinfunction "NC_W18") (pintype "passive+no_connect"))
    )
    (net (code "71") (name "unconnected-(U2H-NC-PadY5)") (class "Default")
      (node (ref "U2") (pin "Y5") (pinfunction "NC_Y5") (pintype "passive+no_connect"))
    )
    (net (code "72") (name "unconnected-(U2H-NC-PadY6)") (class "Default")
      (node (ref "U2") (pin "Y6") (pinfunction "NC_Y6") (pintype "passive+no_connect"))
    )
    (net (code "73") (name "unconnected-(U2H-NC-PadY8)") (class "Default")
      (node (ref "U2") (pin "Y8") (pinfunction "NC_Y8") (pintype "passive+no_connect"))
    )
    (net (code "74") (name "unconnected-(U2H-NC-PadY10)") (class "Default")
      (node (ref "U2") (pin "Y10") (pinfunction "NC_Y10") (pintype "passive+no_connect"))
    )
    (net (code "75") (name "unconnected-(U2H-NC-PadY14)") (class "Default")
      (node (ref "U2") (pin "Y14") (pinfunction "NC_Y14") (pintype "passive+no_connect"))
    )
    (net (code "76") (name "unconnected-(U2H-NC-PadY16)") (class "Default")
      (node (ref "U2") (pin "Y16") (pinfunction "NC_Y16") (pintype "passive+no_connect"))
    )
    (net (code "77") (name "unconnected-(U2H-NC-PadY18)") (class "Default")
      (node (ref "U2") (pin "Y18") (pinfunction "NC_Y18") (pintype "passive+no_connect"))
    )
  )
)
